# 01_Power_Suppy.net
KiCad netlist of a schematic drawn in Altium Designer
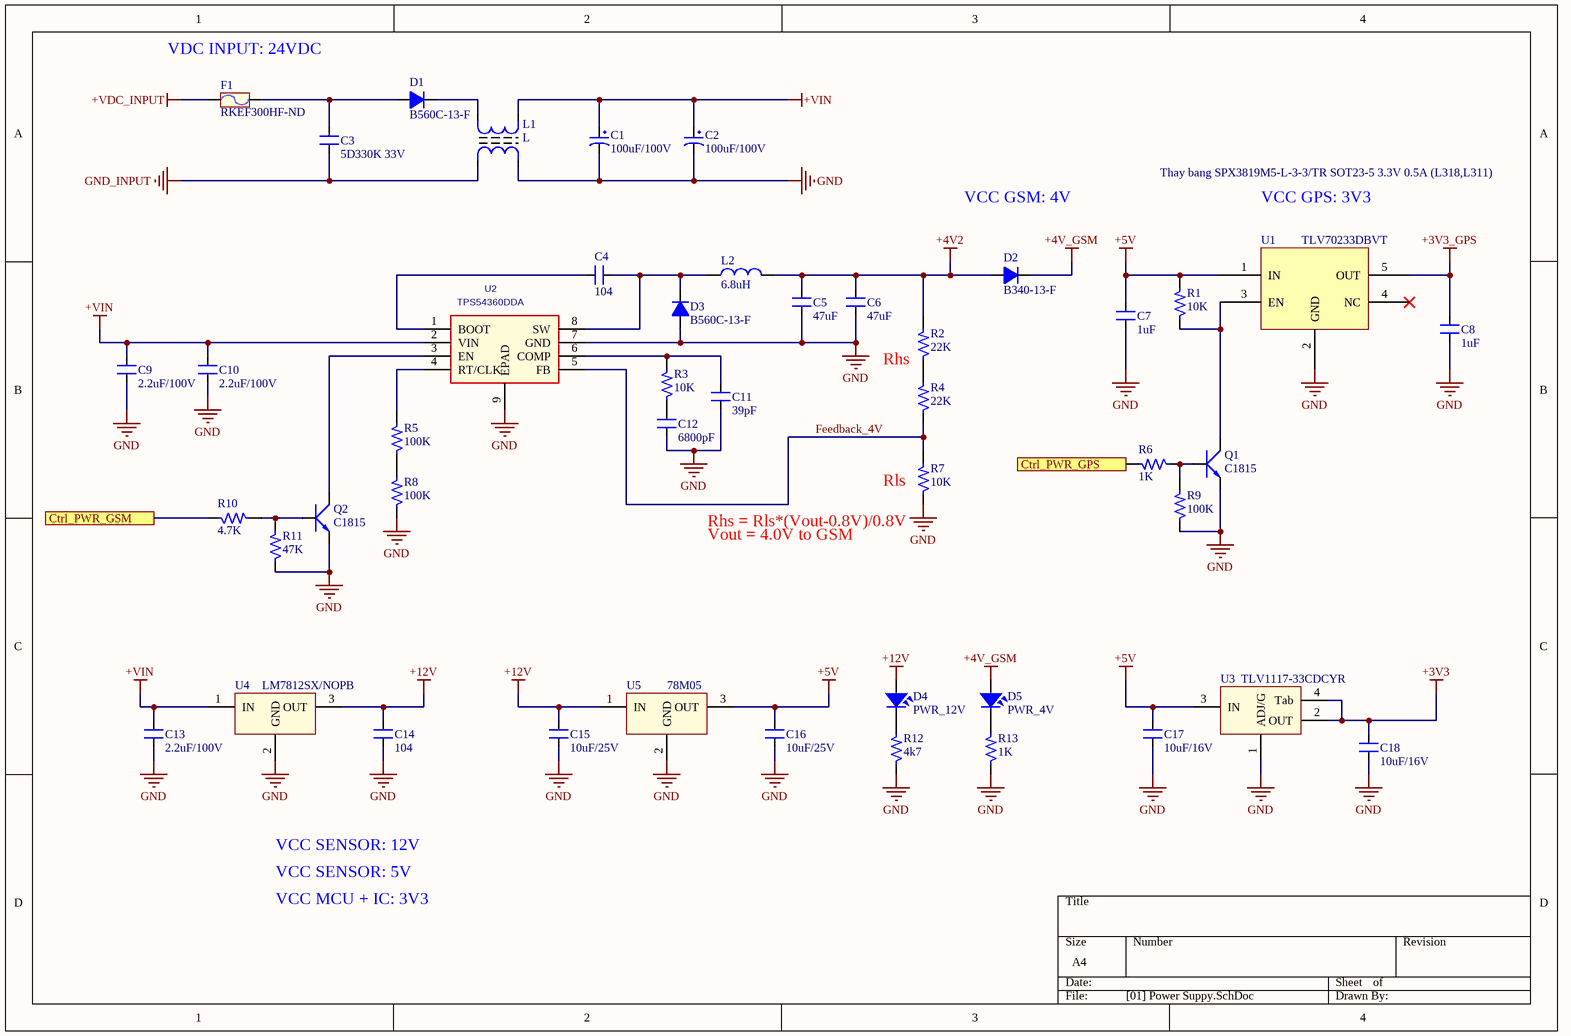
[diagram p0: [01] Power Suppy.SchDoc]

(export (version "E")
  (design (tool "Eeschema 10.0.6"))
  (components
    (comp (ref "C1")
      (value "100uF/100V")
      (footprint "CP1.5/3.4")
      (description "Cap 100uF/35V - 470uF/16V")
      (libsource (lib "syhaunguyen") (part "CP3"))
    )
    (comp (ref "C2")
      (value "100uF/100V")
      (footprint "CP1.5/3.4")
      (description "Cap 100uF/35V - 470uF/16V")
      (libsource (lib "syhaunguyen") (part "CP3"))
    )
    (comp (ref "C3")
      (value "5D330K 33V")
      (footprint "CN2")
      (fields (field (name "DESIGNED BY") "VanDungEvn"))
      (libsource (lib "GPS_Traking_V1_1") (part "CN"))
    )
    (comp (ref "C4")
      (value "104")
      (footprint "C0603 SMT")
      (description "Cap SMD")
      (libsource (lib "GPS_Traking_V1_1") (part "CM_1"))
    )
    (comp (ref "C5")
      (value "47uF")
      (footprint "SM-1210")
      (description "Cap SMD")
      (libsource (lib "GPS_Traking_V1_1") (part "CM_1"))
    )
    (comp (ref "C6")
      (value "47uF")
      (footprint "SM-1210")
      (description "Cap SMD")
      (libsource (lib "GPS_Traking_V1_1") (part "CM_1"))
    )
    (comp (ref "C7")
      (value "1uF")
      (footprint "SM-1210")
      (description "Cap SMD")
      (libsource (lib "GPS_Traking_V1_1") (part "CM_1"))
    )
    (comp (ref "C8")
      (value "1uF")
      (footprint "SM-1210")
      (description "Cap SMD")
      (libsource (lib "GPS_Traking_V1_1") (part "CM_1"))
    )
    (comp (ref "C9")
      (value "2.2uF/100V")
      (footprint "SM-1210")
      (description "CAP CER 2.2UF 100V X7R 1210  445-4498-2-ND")
      (libsource (lib "GPS_Traking_V1_1") (part "CM"))
    )
    (comp (ref "C10")
      (value "2.2uF/100V")
      (footprint "SM-1210")
      (description "CAP CER 2.2UF 100V X7R 1210  445-4498-2-ND")
      (libsource (lib "GPS_Traking_V1_1") (part "CM"))
    )
    (comp (ref "C11")
      (value "39pF")
      (footprint "CAP_0805")
      (description "Cap SMD")
      (libsource (lib "GPS_Traking_V1_1") (part "CM_1"))
    )
    (comp (ref "C12")
      (value "6800pF")
      (footprint "CAP_0805")
      (description "Cap SMD")
      (libsource (lib "GPS_Traking_V1_1") (part "CM_1"))
    )
    (comp (ref "C13")
      (value "2.2uF/100V")
      (footprint "SM-1210")
      (description "CAP CER 2.2UF 100V X7R 1210  445-4498-2-ND")
      (libsource (lib "GPS_Traking_V1_1") (part "CM"))
    )
    (comp (ref "C14")
      (value "104")
      (footprint "CAP_0805")
      (description "Cap SMD")
      (libsource (lib "GPS_Traking_V1_1") (part "CM_1"))
    )
    (comp (ref "C15")
      (value "10uF/25V")
      (footprint "CAP_0805")
      (description "Cap SMD")
      (libsource (lib "GPS_Traking_V1_1") (part "CM_1"))
    )
    (comp (ref "C16")
      (value "10uF/25V")
      (footprint "CAP_0805")
      (description "Cap SMD")
      (libsource (lib "GPS_Traking_V1_1") (part "CM_1"))
    )
    (comp (ref "C17")
      (value "10uF/16V")
      (footprint "CAP_0805")
      (description "Cap SMD")
      (libsource (lib "GPS_Traking_V1_1") (part "CM_1"))
    )
    (comp (ref "C18")
      (value "10uF/16V")
      (footprint "CAP_0805")
      (description "Cap SMD")
      (libsource (lib "GPS_Traking_V1_1") (part "CM_1"))
    )
    (comp (ref "D1")
      (value "B560C-13-F")
      (footprint "DO-214AB SMC")
      (description "DIODE SCHOTTKY 60V 5A SMC")
      (libsource (lib "GPS_Traking_V1_1") (part "D5A"))
    )
    (comp (ref "D2")
      (value "B340-13-F")
      (footprint "DO-214AB SMA")
      (description "DIODE SCHOTTKY 40V 3A SMC")
      (libsource (lib "GPS_Traking_V1_1") (part "D1A"))
    )
    (comp (ref "D3")
      (value "B560C-13-F")
      (footprint "DO-214AB SMC")
      (description "DIODE SCHOTTKY 60V 5A SMC")
      (libsource (lib "GPS_Traking_V1_1") (part "D5A"))
    )
    (comp (ref "D4")
      (value "PWR_12V")
      (footprint "LED-0805-Yellow")
      (description "LED Single colour Green and Red")
      (libsource (lib "GPS_Traking_V1_1") (part "LED"))
    )
    (comp (ref "D5")
      (value "PWR_4V")
      (footprint "LED-0805-Green")
      (description "LED Single colour Green and Red")
      (libsource (lib "GPS_Traking_V1_1") (part "LED"))
    )
    (comp (ref "F1")
      (value "RKEF300HF-ND")
      (footprint "FUSE2")
      (description "PTC RESET FUSE 60V 3A RADIAL")
      (fields (field (name "DESIGNED BY") "VanDungEvn"))
      (libsource (lib "GPS_Traking_V1_1") (part "Fuse"))
    )
    (comp (ref "L1")
      (value "L")
      (footprint "L2 UF9.8")
      (description "Inductor")
      (fields (field (name "DESIGNED BY") "VanDungEvn"))
      (libsource (lib "GPS_Traking_V1_1") (part "L2x220"))
    )
    (comp (ref "L2")
      (value "6.8uH")
      (footprint "L01 SMD 12*12*6")
      (description "FIXED IND 6.2UH 5.7A 22.4 MOHM")
      (libsource (lib "GPS_Traking_V1_1") (part "L1"))
    )
    (comp (ref "Q1")
      (value "C1815")
      (footprint "SOT23B")
      (description "NPN 600mW, ECB")
      (libsource (lib "GPS_Traking_V1_1") (part "C1815"))
    )
    (comp (ref "Q2")
      (value "C1815")
      (footprint "SOT23B")
      (description "NPN 600mW, ECB")
      (libsource (lib "GPS_Traking_V1_1") (part "C1815"))
    )
    (comp (ref "R1")
      (value "10K")
      (footprint "R0603 -SMT")
      (description "Resistor SMD")
      (libsource (lib "GPS_Traking_V1_1") (part "RM"))
    )
    (comp (ref "R2")
      (value "22K")
      (footprint "RES-SMD-0805")
      (description "Resistor SMD")
      (libsource (lib "GPS_Traking_V1_1") (part "RM"))
    )
    (comp (ref "R3")
      (value "10K")
      (footprint "RES-SMD-0805")
      (description "Resistor SMD")
      (libsource (lib "GPS_Traking_V1_1") (part "RM"))
    )
    (comp (ref "R4")
      (value "22K")
      (footprint "RES-SMD-0805")
      (description "Resistor SMD")
      (libsource (lib "GPS_Traking_V1_1") (part "RM"))
    )
    (comp (ref "R5")
      (value "100K")
      (footprint "RES-SMD-0805")
      (description "Resistor SMD")
      (libsource (lib "GPS_Traking_V1_1") (part "RM"))
    )
    (comp (ref "R6")
      (value "1K")
      (footprint "R0603 -SMT")
      (description "Resistor SMD")
      (libsource (lib "GPS_Traking_V1_1") (part "RM"))
    )
    (comp (ref "R7")
      (value "10K")
      (footprint "RES-SMD-0805")
      (description "Resistor SMD")
      (libsource (lib "GPS_Traking_V1_1") (part "RM"))
    )
    (comp (ref "R8")
      (value "100K")
      (footprint "RES-SMD-0805")
      (description "Resistor SMD")
      (libsource (lib "GPS_Traking_V1_1") (part "RM"))
    )
    (comp (ref "R9")
      (value "100K")
      (footprint "R0603 -SMT")
      (description "Resistor SMD")
      (libsource (lib "GPS_Traking_V1_1") (part "RM"))
    )
    (comp (ref "R10")
      (value "4.7K")
      (footprint "RES-SMD-0805")
      (description "Resistor SMD")
      (libsource (lib "GPS_Traking_V1_1") (part "RM"))
    )
    (comp (ref "R11")
      (value "47K")
      (footprint "RES-SMD-0805")
      (description "Resistor SMD")
      (libsource (lib "GPS_Traking_V1_1") (part "RM"))
    )
    (comp (ref "R12")
      (value "4k7")
      (footprint "RES-SMD-0805")
      (description "Resistor SMD")
      (libsource (lib "GPS_Traking_V1_1") (part "RM"))
    )
    (comp (ref "R13")
      (value "1K")
      (footprint "RES-SMD-0805")
      (description "Resistor SMD")
      (libsource (lib "GPS_Traking_V1_1") (part "RM"))
    )
    (comp (ref "U1")
      (value "TLV70233DBVT")
      (footprint "TLV70233_3.3V")
      (libsource (lib "GPS_Traking_V1_1") (part "TLV70233_3.3V"))
    )
    (comp (ref "U2")
      (value "TPS54360DDA")
      (footprint "DDA8_3P1X2P4-M")
      (description "REG BUCK SPLIT RAIL 8SOPWRPAD")
      (libsource (lib "GPS_Traking_V1_1") (part "TPS54360DDA"))
    )
    (comp (ref "U3")
      (value "TLV1117-33CDCYR")
      (footprint "SOT223-4N")
      (description "3v3")
      (libsource (lib "GPS_Traking_V1_1") (part "LM1117"))
    )
    (comp (ref "U4")
      (value "LM7812SX/NOPB")
      (footprint "TO-263-4")
      (libsource (lib "GPS_Traking_V1_1") (part "LM78xx_1"))
    )
    (comp (ref "U5")
      (value "78M05")
      (footprint "TO252-3L")
      (description "On ap +, from + 5 to + 24VDC")
      (libsource (lib "GPS_Traking_V1_1") (part "LM78xx"))
    )
  )
  (nets
    (net (code "1") (name "+3V3") (class "Default")
      (node (ref "C18") (pin "2") (pinfunction "2_2") (pintype "passive"))
      (node (ref "U3") (pin "2") (pinfunction "OUT_2") (pintype "passive"))
      (node (ref "U3") (pin "4") (pinfunction "Tab_4") (pintype "passive"))
    )
    (net (code "2") (name "+3V3_GPS") (class "Default")
      (node (ref "C8") (pin "2") (pinfunction "2_2") (pintype "passive"))
      (node (ref "U1") (pin "5") (pinfunction "OUT_5") (pintype "passive"))
    )
    (net (code "3") (name "+4V2") (class "Default")
      (node (ref "C5") (pin "2") (pinfunction "2_2") (pintype "passive"))
      (node (ref "C6") (pin "2") (pinfunction "2_2") (pintype "passive"))
      (node (ref "D2") (pin "1") (pinfunction "A_1") (pintype "passive"))
      (node (ref "L2") (pin "2") (pinfunction "2_2") (pintype "passive"))
      (node (ref "R2") (pin "2") (pinfunction "2_2") (pintype "passive"))
    )
    (net (code "4") (name "+4V_GSM") (class "Default")
      (node (ref "D2") (pin "2") (pinfunction "K_2") (pintype "passive"))
      (node (ref "D5") (pin "1") (pinfunction "1_1") (pintype "passive"))
    )
    (net (code "5") (name "+5V") (class "Default")
      (node (ref "C16") (pin "2") (pinfunction "2_2") (pintype "passive"))
      (node (ref "C17") (pin "2") (pinfunction "2_2") (pintype "passive"))
      (node (ref "C7") (pin "2") (pinfunction "2_2") (pintype "passive"))
      (node (ref "R1") (pin "2") (pinfunction "2_2") (pintype "passive"))
      (node (ref "U1") (pin "1") (pinfunction "IN_1") (pintype "passive"))
      (node (ref "U3") (pin "3") (pinfunction "IN_3") (pintype "passive"))
      (node (ref "U5") (pin "3") (pinfunction "OUT_3") (pintype "passive"))
    )
    (net (code "6") (name "+12V") (class "Default")
      (node (ref "C14") (pin "2") (pinfunction "2_2") (pintype "passive"))
      (node (ref "C15") (pin "2") (pinfunction "2_2") (pintype "passive"))
      (node (ref "D4") (pin "1") (pinfunction "1_1") (pintype "passive"))
      (node (ref "U4") (pin "3") (pinfunction "OUT_3") (pintype "passive"))
      (node (ref "U5") (pin "1") (pinfunction "IN_1") (pintype "passive"))
    )
    (net (code "7") (name "+VDC_INPUT") (class "Default")
      (node (ref "F1") (pin "1") (pinfunction "1_1") (pintype "passive"))
    )
    (net (code "8") (name "+VIN") (class "Default")
      (node (ref "C1") (pin "1") (pinfunction "1_1") (pintype "passive"))
      (node (ref "C10") (pin "2") (pinfunction "2_2") (pintype "passive"))
      (node (ref "C13") (pin "2") (pinfunction "2_2") (pintype "passive"))
      (node (ref "C2") (pin "1") (pinfunction "1_1") (pintype "passive"))
      (node (ref "C9") (pin "2") (pinfunction "2_2") (pintype "passive"))
      (node (ref "L1") (pin "3") (pinfunction "3_3") (pintype "passive"))
      (node (ref "U2") (pin "2") (pinfunction "VIN_2") (pintype "passive"))
      (node (ref "U4") (pin "1") (pinfunction "IN_1") (pintype "passive"))
    )
    (net (code "9") (name "/Ctrl_PWR_GPS") (class "Default")
      (node (ref "R6") (pin "2") (pinfunction "2_2") (pintype "passive"))
    )
    (net (code "10") (name "/Ctrl_PWR_GSM") (class "Default")
      (node (ref "R10") (pin "1") (pinfunction "1_1") (pintype "passive"))
    )
    (net (code "11") (name "/Feedback_4V") (class "Default")
      (node (ref "R4") (pin "1") (pinfunction "1_1") (pintype "passive"))
      (node (ref "R7") (pin "2") (pinfunction "2_2") (pintype "passive"))
      (node (ref "U2") (pin "5") (pinfunction "FB_5") (pintype "passive"))
    )
    (net (code "12") (name "GND") (class "Default")
      (node (ref "C1") (pin "2") (pinfunction "2_2") (pintype "passive"))
      (node (ref "C10") (pin "1") (pinfunction "1_1") (pintype "passive"))
      (node (ref "C11") (pin "1") (pinfunction "1_1") (pintype "passive"))
      (node (ref "C12") (pin "1") (pinfunction "1_1") (pintype "passive"))
      (node (ref "C13") (pin "1") (pinfunction "1_1") (pintype "passive"))
      (node (ref "C14") (pin "1") (pinfunction "1_1") (pintype "passive"))
      (node (ref "C15") (pin "1") (pinfunction "1_1") (pintype "passive"))
      (node (ref "C16") (pin "1") (pinfunction "1_1") (pintype "passive"))
      (node (ref "C17") (pin "1") (pinfunction "1_1") (pintype "passive"))
      (node (ref "C18") (pin "1") (pinfunction "1_1") (pintype "passive"))
      (node (ref "C2") (pin "2") (pinfunction "2_2") (pintype "passive"))
      (node (ref "C5") (pin "1") (pinfunction "1_1") (pintype "passive"))
      (node (ref "C6") (pin "1") (pinfunction "1_1") (pintype "passive"))
      (node (ref "C7") (pin "1") (pinfunction "1_1") (pintype "passive"))
      (node (ref "C8") (pin "1") (pinfunction "1_1") (pintype "passive"))
      (node (ref "C9") (pin "1") (pinfunction "1_1") (pintype "passive"))
      (node (ref "D3") (pin "1") (pinfunction "A_1") (pintype "passive"))
      (node (ref "L1") (pin "2") (pinfunction "2_2") (pintype "passive"))
      (node (ref "Q1") (pin "1") (pinfunction "E_1") (pintype "passive"))
      (node (ref "Q2") (pin "1") (pinfunction "E_1") (pintype "passive"))
      (node (ref "R11") (pin "1") (pinfunction "1_1") (pintype "passive"))
      (node (ref "R12") (pin "1") (pinfunction "1_1") (pintype "passive"))
      (node (ref "R13") (pin "1") (pinfunction "1_1") (pintype "passive"))
      (node (ref "R7") (pin "1") (pinfunction "1_1") (pintype "passive"))
      (node (ref "R8") (pin "1") (pinfunction "1_1") (pintype "passive"))
      (node (ref "R9") (pin "1") (pinfunction "1_1") (pintype "passive"))
      (node (ref "U1") (pin "2") (pinfunction "GND_2") (pintype "power_in"))
      (node (ref "U2") (pin "7") (pinfunction "GND_7") (pintype "passive"))
      (node (ref "U2") (pin "9") (pinfunction "EPAD_9") (pintype "passive"))
      (node (ref "U3") (pin "1") (pinfunction "ADJ/G_1") (pintype "passive"))
      (node (ref "U4") (pin "2") (pinfunction "GND_2") (pintype "passive"))
      (node (ref "U5") (pin "2") (pinfunction "GND_2") (pintype "passive"))
    )
    (net (code "13") (name "GND_INPUT") (class "Default")
      (node (ref "C3") (pin "1") (pinfunction "1_1") (pintype "passive"))
      (node (ref "L1") (pin "1") (pinfunction "1_1") (pintype "passive"))
    )
    (net (code "14") (name "Net-(C12-Pad2)") (class "Default")
      (node (ref "C12") (pin "2") (pinfunction "2_2") (pintype "passive"))
      (node (ref "R3") (pin "1") (pinfunction "1_1") (pintype "passive"))
    )
    (net (code "15") (name "Net-(D1-A)") (class "Default")
      (node (ref "C3") (pin "2") (pinfunction "2_2") (pintype "passive"))
      (node (ref "D1") (pin "1") (pinfunction "A_1") (pintype "passive"))
      (node (ref "F1") (pin "2") (pinfunction "2_2") (pintype "passive"))
    )
    (net (code "16") (name "Net-(D1-K)") (class "Default")
      (node (ref "D1") (pin "2") (pinfunction "K_2") (pintype "passive"))
      (node (ref "L1") (pin "4") (pinfunction "4_4") (pintype "passive"))
    )
    (net (code "17") (name "Net-(D3-K)") (class "Default")
      (node (ref "C4") (pin "2") (pinfunction "2_2") (pintype "passive"))
      (node (ref "D3") (pin "2") (pinfunction "K_2") (pintype "passive"))
      (node (ref "L2") (pin "1") (pinfunction "1_1") (pintype "passive"))
      (node (ref "U2") (pin "8") (pinfunction "SW_8") (pintype "passive"))
    )
    (net (code "18") (name "Net-(D4-Pad2)") (class "Default")
      (node (ref "D4") (pin "2") (pinfunction "2_2") (pintype "passive"))
      (node (ref "R12") (pin "2") (pinfunction "2_2") (pintype "passive"))
    )
    (net (code "19") (name "Net-(D5-Pad2)") (class "Default")
      (node (ref "D5") (pin "2") (pinfunction "2_2") (pintype "passive"))
      (node (ref "R13") (pin "2") (pinfunction "2_2") (pintype "passive"))
    )
    (net (code "20") (name "Net-(Q1-B)") (class "Default")
      (node (ref "Q1") (pin "3") (pinfunction "B_3") (pintype "passive"))
      (node (ref "R6") (pin "1") (pinfunction "1_1") (pintype "passive"))
      (node (ref "R9") (pin "2") (pinfunction "2_2") (pintype "passive"))
    )
    (net (code "21") (name "Net-(Q1-C)") (class "Default")
      (node (ref "Q1") (pin "2") (pinfunction "C_2") (pintype "passive"))
      (node (ref "R1") (pin "1") (pinfunction "1_1") (pintype "passive"))
      (node (ref "U1") (pin "3") (pinfunction "EN_3") (pintype "passive"))
    )
    (net (code "22") (name "Net-(Q2-B)") (class "Default")
      (node (ref "Q2") (pin "3") (pinfunction "B_3") (pintype "passive"))
      (node (ref "R10") (pin "2") (pinfunction "2_2") (pintype "passive"))
      (node (ref "R11") (pin "2") (pinfunction "2_2") (pintype "passive"))
    )
    (net (code "23") (name "Net-(Q2-C)") (class "Default")
      (node (ref "Q2") (pin "2") (pinfunction "C_2") (pintype "passive"))
      (node (ref "U2") (pin "3") (pinfunction "EN_3") (pintype "passive"))
    )
    (net (code "24") (name "Net-(R2-Pad1)") (class "Default")
      (node (ref "R2") (pin "1") (pinfunction "1_1") (pintype "passive"))
      (node (ref "R4") (pin "2") (pinfunction "2_2") (pintype "passive"))
    )
    (net (code "25") (name "Net-(R5-Pad1)") (class "Default")
      (node (ref "R5") (pin "1") (pinfunction "1_1") (pintype "passive"))
      (node (ref "R8") (pin "2") (pinfunction "2_2") (pintype "passive"))
    )
    (net (code "26") (name "Net-(U2-BOOT)") (class "Default")
      (node (ref "C4") (pin "1") (pinfunction "1_1") (pintype "passive"))
      (node (ref "U2") (pin "1") (pinfunction "BOOT_1") (pintype "passive"))
    )
    (net (code "27") (name "Net-(U2-COMP)") (class "Default")
      (node (ref "C11") (pin "2") (pinfunction "2_2") (pintype "passive"))
      (node (ref "R3") (pin "2") (pinfunction "2_2") (pintype "passive"))
      (node (ref "U2") (pin "6") (pinfunction "COMP_6") (pintype "passive"))
    )
    (net (code "28") (name "Net-(U2-RT{slash}CLK)") (class "Default")
      (node (ref "R5") (pin "2") (pinfunction "2_2") (pintype "passive"))
      (node (ref "U2") (pin "4") (pinfunction "RT/CLK_4") (pintype "passive"))
    )
    (net (code "29") (name "unconnected-(U1-NC-Pad4)") (class "Default")
      (node (ref "U1") (pin "4") (pinfunction "NC_4") (pintype "passive+no_connect"))
    )
  )
)
